# Pi_Hat.net
KiCad netlist of a schematic drawn in EAGLE
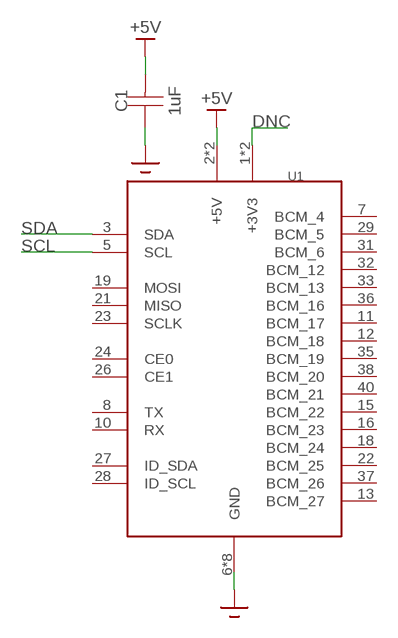
[diagram p0: schematic, sheet 1]
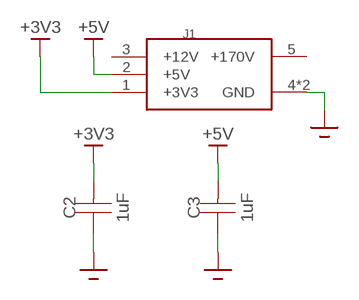
[diagram p1: schematic, sheet 2]
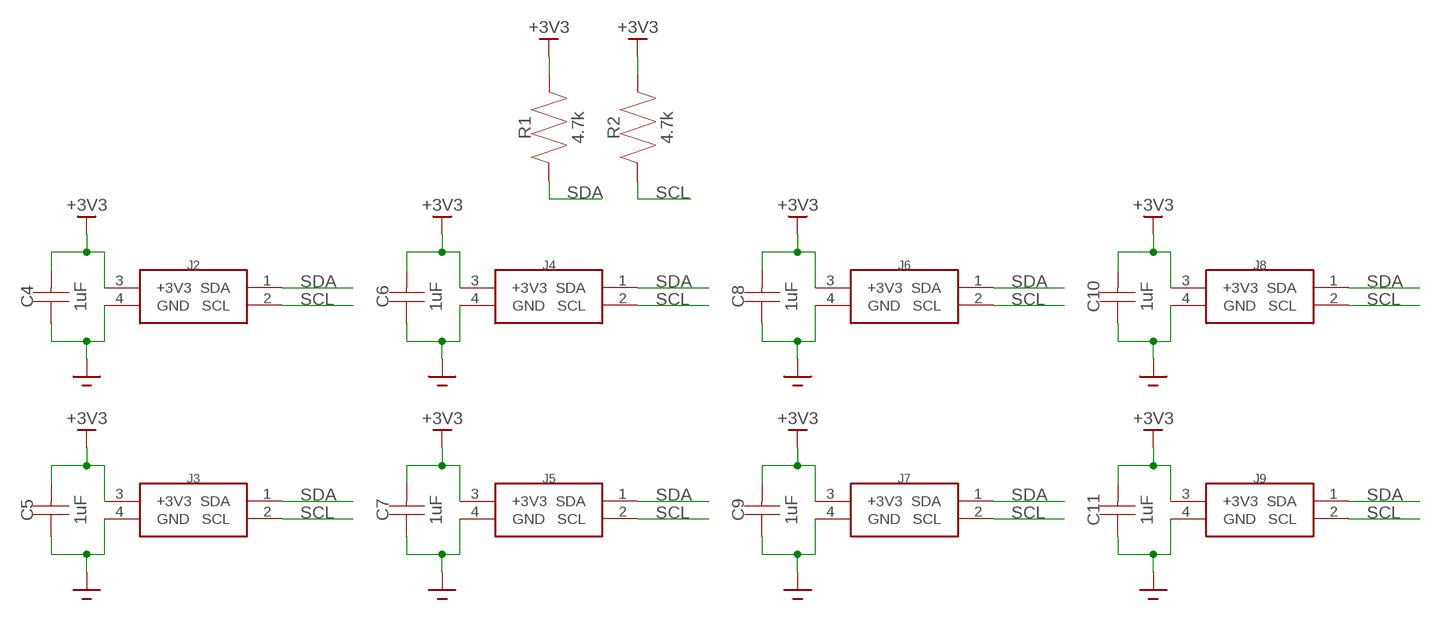
[diagram p2: schematic, sheet 3]

(export (version "E")
  (design (tool "Eeschema 10.0.6"))
  (components
    (comp (ref "C1")
      (value "1uF")
      (footprint "eagle-import:0805")
      (libsource (lib "eagle-import") (part "CAPACITOR0805"))
    )
    (comp (ref "U1")
      (value "RPI")
      (footprint "eagle-import:RPI")
      (libsource (lib "eagle-import") (part "RPI"))
    )
    (comp (ref "C4")
      (value "1uF")
      (footprint "eagle-import:0805")
      (libsource (lib "eagle-import") (part "CAPACITOR0805"))
    )
    (comp (ref "C5")
      (value "1uF")
      (footprint "eagle-import:0805")
      (libsource (lib "eagle-import") (part "CAPACITOR0805"))
    )
    (comp (ref "C6")
      (value "1uF")
      (footprint "eagle-import:0805")
      (libsource (lib "eagle-import") (part "CAPACITOR0805"))
    )
    (comp (ref "C7")
      (value "1uF")
      (footprint "eagle-import:0805")
      (libsource (lib "eagle-import") (part "CAPACITOR0805"))
    )
    (comp (ref "C8")
      (value "1uF")
      (footprint "eagle-import:0805")
      (libsource (lib "eagle-import") (part "CAPACITOR0805"))
    )
    (comp (ref "C9")
      (value "1uF")
      (footprint "eagle-import:0805")
      (libsource (lib "eagle-import") (part "CAPACITOR0805"))
    )
    (comp (ref "C10")
      (value "1uF")
      (footprint "eagle-import:0805")
      (libsource (lib "eagle-import") (part "CAPACITOR0805"))
    )
    (comp (ref "C11")
      (value "1uF")
      (footprint "eagle-import:0805")
      (libsource (lib "eagle-import") (part "CAPACITOR0805"))
    )
    (comp (ref "J2")
      (value "1-770968-0")
      (footprint "eagle-import:1-770968-0")
      (libsource (lib "eagle-import") (part "1-770968-0"))
    )
    (comp (ref "J3")
      (value "1-770968-0")
      (footprint "eagle-import:1-770968-0")
      (libsource (lib "eagle-import") (part "1-770968-0"))
    )
    (comp (ref "J4")
      (value "1-770968-0")
      (footprint "eagle-import:1-770968-0")
      (libsource (lib "eagle-import") (part "1-770968-0"))
    )
    (comp (ref "J5")
      (value "1-770968-0")
      (footprint "eagle-import:1-770968-0")
      (libsource (lib "eagle-import") (part "1-770968-0"))
    )
    (comp (ref "J6")
      (value "1-770968-0")
      (footprint "eagle-import:1-770968-0")
      (libsource (lib "eagle-import") (part "1-770968-0"))
    )
    (comp (ref "J7")
      (value "1-770968-0")
      (footprint "eagle-import:1-770968-0")
      (libsource (lib "eagle-import") (part "1-770968-0"))
    )
    (comp (ref "J8")
      (value "1-770968-0")
      (footprint "eagle-import:1-770968-0")
      (libsource (lib "eagle-import") (part "1-770968-0"))
    )
    (comp (ref "J9")
      (value "1-770968-0")
      (footprint "eagle-import:1-770968-0")
      (libsource (lib "eagle-import") (part "1-770968-0"))
    )
    (comp (ref "R1")
      (value "4.7k")
      (footprint "eagle-import:0805")
      (libsource (lib "eagle-import") (part "RESISTOR0805"))
    )
    (comp (ref "R2")
      (value "4.7k")
      (footprint "eagle-import:0805")
      (libsource (lib "eagle-import") (part "RESISTOR0805"))
    )
    (comp (ref "C2")
      (value "1uF")
      (footprint "eagle-import:0805")
      (libsource (lib "eagle-import") (part "CAPACITOR0805"))
    )
    (comp (ref "C3")
      (value "1uF")
      (footprint "eagle-import:0805")
      (libsource (lib "eagle-import") (part "CAPACITOR0805"))
    )
    (comp (ref "J1")
      (value "1-770969-0")
      (footprint "eagle-import:1-770969-0")
      (libsource (lib "eagle-import") (part "1-770969-0"))
    )
  )
  (nets
    (net (code "1") (name "+3V3") (class "Default")
      (node (ref "C10") (pin "P$2") (pinfunction "P$2_P$2") (pintype "passive"))
      (node (ref "C11") (pin "P$2") (pinfunction "P$2_P$2") (pintype "passive"))
      (node (ref "C2") (pin "P$2") (pinfunction "P$2_P$2") (pintype "passive"))
      (node (ref "C4") (pin "P$2") (pinfunction "P$2_P$2") (pintype "passive"))
      (node (ref "C5") (pin "P$2") (pinfunction "P$2_P$2") (pintype "passive"))
      (node (ref "C6") (pin "P$2") (pinfunction "P$2_P$2") (pintype "passive"))
      (node (ref "C7") (pin "P$2") (pinfunction "P$2_P$2") (pintype "passive"))
      (node (ref "C8") (pin "P$2") (pinfunction "P$2_P$2") (pintype "passive"))
      (node (ref "C9") (pin "P$2") (pinfunction "P$2_P$2") (pintype "passive"))
      (node (ref "J1") (pin "1") (pinfunction "+3V3_1") (pintype "power_in"))
      (node (ref "J2") (pin "3") (pinfunction "+3V3_3") (pintype "power_in"))
      (node (ref "J3") (pin "3") (pinfunction "+3V3_3") (pintype "power_in"))
      (node (ref "J4") (pin "3") (pinfunction "+3V3_3") (pintype "power_in"))
      (node (ref "J5") (pin "3") (pinfunction "+3V3_3") (pintype "power_in"))
      (node (ref "J6") (pin "3") (pinfunction "+3V3_3") (pintype "power_in"))
      (node (ref "J7") (pin "3") (pinfunction "+3V3_3") (pintype "power_in"))
      (node (ref "J8") (pin "3") (pinfunction "+3V3_3") (pintype "power_in"))
      (node (ref "J9") (pin "3") (pinfunction "+3V3_3") (pintype "power_in"))
      (node (ref "R1") (pin "P$2") (pinfunction "P$2_P$2") (pintype "passive"))
      (node (ref "R2") (pin "P$2") (pinfunction "P$2_P$2") (pintype "passive"))
    )
    (net (code "2") (name "+5V") (class "Default")
      (node (ref "C1") (pin "P$2") (pinfunction "P$2_P$2") (pintype "passive"))
      (node (ref "C3") (pin "P$2") (pinfunction "P$2_P$2") (pintype "passive"))
      (node (ref "J1") (pin "2") (pinfunction "+5V_2") (pintype "power_in"))
      (node (ref "U1") (pin "2") (pinfunction "+5V_2") (pintype "power_in"))
      (node (ref "U1") (pin "4") (pinfunction "+5V_4") (pintype "power_in"))
    )
    (net (code "3") (name "+12V") (class "Default")
      (node (ref "J1") (pin "3") (pinfunction "+12V_3") (pintype "power_in"))
    )
    (net (code "4") (name "+170V") (class "Default")
      (node (ref "J1") (pin "5") (pinfunction "+170V_5") (pintype "power_in"))
    )
    (net (code "5") (name "DNC") (class "Default")
      (node (ref "U1") (pin "1") (pinfunction "+3V3_1") (pintype "power_in"))
      (node (ref "U1") (pin "17") (pinfunction "+3V3_17") (pintype "power_in"))
    )
    (net (code "6") (name "GND") (class "Default")
      (node (ref "C1") (pin "P$1") (pinfunction "P$1_P$1") (pintype "passive"))
      (node (ref "C10") (pin "P$1") (pinfunction "P$1_P$1") (pintype "passive"))
      (node (ref "C11") (pin "P$1") (pinfunction "P$1_P$1") (pintype "passive"))
      (node (ref "C2") (pin "P$1") (pinfunction "P$1_P$1") (pintype "passive"))
      (node (ref "C3") (pin "P$1") (pinfunction "P$1_P$1") (pintype "passive"))
      (node (ref "C4") (pin "P$1") (pinfunction "P$1_P$1") (pintype "passive"))
      (node (ref "C5") (pin "P$1") (pinfunction "P$1_P$1") (pintype "passive"))
      (node (ref "C6") (pin "P$1") (pinfunction "P$1_P$1") (pintype "passive"))
      (node (ref "C7") (pin "P$1") (pinfunction "P$1_P$1") (pintype "passive"))
      (node (ref "C8") (pin "P$1") (pinfunction "P$1_P$1") (pintype "passive"))
      (node (ref "C9") (pin "P$1") (pinfunction "P$1_P$1") (pintype "passive"))
      (node (ref "J1") (pin "4") (pinfunction "GND_4") (pintype "passive"))
      (node (ref "J1") (pin "6") (pinfunction "GND_6") (pintype "passive"))
      (node (ref "J2") (pin "4") (pinfunction "GND_4") (pintype "passive"))
      (node (ref "J3") (pin "4") (pinfunction "GND_4") (pintype "passive"))
      (node (ref "J4") (pin "4") (pinfunction "GND_4") (pintype "passive"))
      (node (ref "J5") (pin "4") (pinfunction "GND_4") (pintype "passive"))
      (node (ref "J6") (pin "4") (pinfunction "GND_4") (pintype "passive"))
      (node (ref "J7") (pin "4") (pinfunction "GND_4") (pintype "passive"))
      (node (ref "J8") (pin "4") (pinfunction "GND_4") (pintype "passive"))
      (node (ref "J9") (pin "4") (pinfunction "GND_4") (pintype "passive"))
      (node (ref "U1") (pin "14") (pinfunction "GND_14") (pintype "passive"))
      (node (ref "U1") (pin "20") (pinfunction "GND_20") (pintype "passive"))
      (node (ref "U1") (pin "25") (pinfunction "GND_25") (pintype "passive"))
      (node (ref "U1") (pin "30") (pinfunction "GND_30") (pintype "passive"))
      (node (ref "U1") (pin "34") (pinfunction "GND_34") (pintype "passive"))
      (node (ref "U1") (pin "39") (pinfunction "GND_39") (pintype "passive"))
      (node (ref "U1") (pin "6") (pinfunction "GND_6") (pintype "passive"))
      (node (ref "U1") (pin "9") (pinfunction "GND_9") (pintype "passive"))
    )
    (net (code "7") (name "SCL") (class "Default")
      (node (ref "J2") (pin "2") (pinfunction "SCL_2") (pintype "bidirectional"))
      (node (ref "J3") (pin "2") (pinfunction "SCL_2") (pintype "bidirectional"))
      (node (ref "J4") (pin "2") (pinfunction "SCL_2") (pintype "bidirectional"))
      (node (ref "J5") (pin "2") (pinfunction "SCL_2") (pintype "bidirectional"))
      (node (ref "J6") (pin "2") (pinfunction "SCL_2") (pintype "bidirectional"))
      (node (ref "J7") (pin "2") (pinfunction "SCL_2") (pintype "bidirectional"))
      (node (ref "J8") (pin "2") (pinfunction "SCL_2") (pintype "bidirectional"))
      (node (ref "J9") (pin "2") (pinfunction "SCL_2") (pintype "bidirectional"))
      (node (ref "R2") (pin "P$1") (pinfunction "P$1_P$1") (pintype "passive"))
      (node (ref "U1") (pin "5") (pinfunction "SCL_5") (pintype "bidirectional"))
    )
    (net (code "8") (name "SDA") (class "Default")
      (node (ref "J2") (pin "1") (pinfunction "SDA_1") (pintype "bidirectional"))
      (node (ref "J3") (pin "1") (pinfunction "SDA_1") (pintype "bidirectional"))
      (node (ref "J4") (pin "1") (pinfunction "SDA_1") (pintype "bidirectional"))
      (node (ref "J5") (pin "1") (pinfunction "SDA_1") (pintype "bidirectional"))
      (node (ref "J6") (pin "1") (pinfunction "SDA_1") (pintype "bidirectional"))
      (node (ref "J7") (pin "1") (pinfunction "SDA_1") (pintype "bidirectional"))
      (node (ref "J8") (pin "1") (pinfunction "SDA_1") (pintype "bidirectional"))
      (node (ref "J9") (pin "1") (pinfunction "SDA_1") (pintype "bidirectional"))
      (node (ref "R1") (pin "P$1") (pinfunction "P$1_P$1") (pintype "passive"))
      (node (ref "U1") (pin "3") (pinfunction "SDA_3") (pintype "bidirectional"))
    )
    (net (code "9") (name "unconnected-(U1-BCM_4-Pad7)") (class "Default")
      (node (ref "U1") (pin "7") (pinfunction "BCM_4_7") (pintype "bidirectional"))
    )
    (net (code "10") (name "unconnected-(U1-BCM_5-Pad29)") (class "Default")
      (node (ref "U1") (pin "29") (pinfunction "BCM_5_29") (pintype "bidirectional"))
    )
    (net (code "11") (name "unconnected-(U1-BCM_6-Pad31)") (class "Default")
      (node (ref "U1") (pin "31") (pinfunction "BCM_6_31") (pintype "bidirectional"))
    )
    (net (code "12") (name "unconnected-(U1-BCM_12-Pad32)") (class "Default")
      (node (ref "U1") (pin "32") (pinfunction "BCM_12_32") (pintype "bidirectional"))
    )
    (net (code "13") (name "unconnected-(U1-BCM_13-Pad33)") (class "Default")
      (node (ref "U1") (pin "33") (pinfunction "BCM_13_33") (pintype "bidirectional"))
    )
    (net (code "14") (name "unconnected-(U1-BCM_16-Pad36)") (class "Default")
      (node (ref "U1") (pin "36") (pinfunction "BCM_16_36") (pintype "bidirectional"))
    )
    (net (code "15") (name "unconnected-(U1-BCM_17-Pad11)") (class "Default")
      (node (ref "U1") (pin "11") (pinfunction "BCM_17_11") (pintype "bidirectional"))
    )
    (net (code "16") (name "unconnected-(U1-BCM_18-Pad12)") (class "Default")
      (node (ref "U1") (pin "12") (pinfunction "BCM_18_12") (pintype "bidirectional"))
    )
    (net (code "17") (name "unconnected-(U1-BCM_19-Pad35)") (class "Default")
      (node (ref "U1") (pin "35") (pinfunction "BCM_19_35") (pintype "bidirectional"))
    )
    (net (code "18") (name "unconnected-(U1-BCM_20-Pad38)") (class "Default")
      (node (ref "U1") (pin "38") (pinfunction "BCM_20_38") (pintype "bidirectional"))
    )
    (net (code "19") (name "unconnected-(U1-BCM_21-Pad40)") (class "Default")
      (node (ref "U1") (pin "40") (pinfunction "BCM_21_40") (pintype "bidirectional"))
    )
    (net (code "20") (name "unconnected-(U1-BCM_22-Pad15)") (class "Default")
      (node (ref "U1") (pin "15") (pinfunction "BCM_22_15") (pintype "bidirectional"))
    )
    (net (code "21") (name "unconnected-(U1-BCM_23-Pad16)") (class "Default")
      (node (ref "U1") (pin "16") (pinfunction "BCM_23_16") (pintype "bidirectional"))
    )
    (net (code "22") (name "unconnected-(U1-BCM_24-Pad18)") (class "Default")
      (node (ref "U1") (pin "18") (pinfunction "BCM_24_18") (pintype "bidirectional"))
    )
    (net (code "23") (name "unconnected-(U1-BCM_25-Pad22)") (class "Default")
      (node (ref "U1") (pin "22") (pinfunction "BCM_25_22") (pintype "bidirectional"))
    )
    (net (code "24") (name "unconnected-(U1-BCM_26-Pad37)") (class "Default")
      (node (ref "U1") (pin "37") (pinfunction "BCM_26_37") (pintype "bidirectional"))
    )
    (net (code "25") (name "unconnected-(U1-BCM_27-Pad13)") (class "Default")
      (node (ref "U1") (pin "13") (pinfunction "BCM_27_13") (pintype "bidirectional"))
    )
    (net (code "26") (name "unconnected-(U1-CE0-Pad24)") (class "Default")
      (node (ref "U1") (pin "24") (pinfunction "CE0_24") (pintype "bidirectional"))
    )
    (net (code "27") (name "unconnected-(U1-CE1-Pad26)") (class "Default")
      (node (ref "U1") (pin "26") (pinfunction "CE1_26") (pintype "bidirectional"))
    )
    (net (code "28") (name "unconnected-(U1-ID_SCL-Pad28)") (class "Default")
      (node (ref "U1") (pin "28") (pinfunction "ID_SCL_28") (pintype "bidirectional"))
    )
    (net (code "29") (name "unconnected-(U1-ID_SDA-Pad27)") (class "Default")
      (node (ref "U1") (pin "27") (pinfunction "ID_SDA_27") (pintype "bidirectional"))
    )
    (net (code "30") (name "unconnected-(U1-MISO-Pad21)") (class "Default")
      (node (ref "U1") (pin "21") (pinfunction "MISO_21") (pintype "bidirectional"))
    )
    (net (code "31") (name "unconnected-(U1-MOSI-Pad19)") (class "Default")
      (node (ref "U1") (pin "19") (pinfunction "MOSI_19") (pintype "bidirectional"))
    )
    (net (code "32") (name "unconnected-(U1-RX-Pad10)") (class "Default")
      (node (ref "U1") (pin "10") (pinfunction "RX_10") (pintype "bidirectional"))
    )
    (net (code "33") (name "unconnected-(U1-SCLK-Pad23)") (class "Default")
      (node (ref "U1") (pin "23") (pinfunction "SCLK_23") (pintype "bidirectional"))
    )
    (net (code "34") (name "unconnected-(U1-TX-Pad8)") (class "Default")
      (node (ref "U1") (pin "8") (pinfunction "TX_8") (pintype "bidirectional"))
    )
  )
)
